# Minduino_A.net
KiCad netlist of a schematic drawn in EAGLE
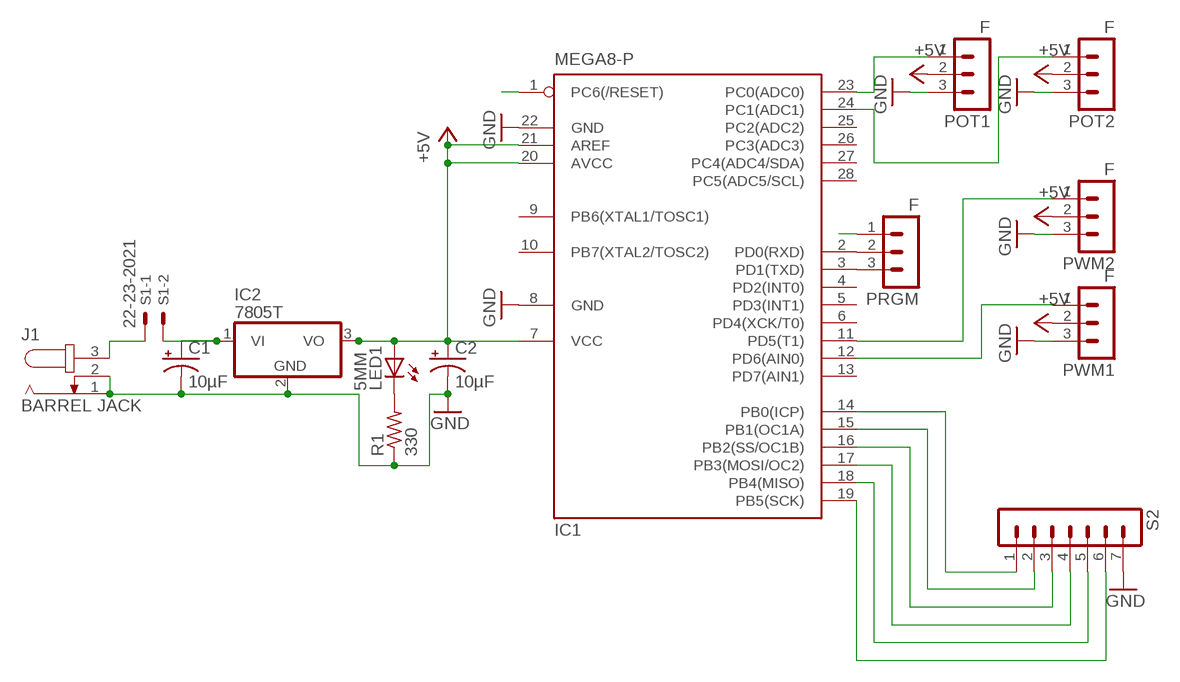
[diagram p0: schematic, sheet 1]

(export (version "E")
  (design (tool "Eeschema 10.0.6"))
  (components
    (comp (ref "C1")
      (value "10µF")
      (footprint "eagle-import:E2,5-5")
      (libsource (lib "eagle-import") (part "CPOL-USE2.5-5"))
    )
    (comp (ref "C2")
      (value "10µF")
      (footprint "eagle-import:E2,5-5")
      (libsource (lib "eagle-import") (part "CPOL-USE2.5-5"))
    )
    (comp (ref "IC1")
      (value "MEGA8-P")
      (footprint "eagle-import:DIL28-3")
      (libsource (lib "eagle-import") (part "MEGA8-P"))
    )
    (comp (ref "IC2")
      (value "7805T")
      (footprint "eagle-import:TO220H")
      (libsource (lib "eagle-import") (part "78T05"))
    )
    (comp (ref "J1")
      (value "BARREL JACK")
      (footprint "eagle-import:SPC4078")
      (libsource (lib "eagle-import") (part "JACK-PLUG1"))
    )
    (comp (ref "LED1")
      (value "5MM")
      (footprint "eagle-import:LED5MM")
      (libsource (lib "eagle-import") (part "LED5MM"))
    )
    (comp (ref "POT1")
      (value "F")
      (footprint "eagle-import:MA03-1")
      (libsource (lib "eagle-import") (part "MA03-1"))
    )
    (comp (ref "POT2")
      (value "F")
      (footprint "eagle-import:MA03-1")
      (libsource (lib "eagle-import") (part "MA03-1"))
    )
    (comp (ref "PRGM")
      (value "F")
      (footprint "eagle-import:MA03-1")
      (fields (field (name "OC_FARNELL") "unknown") (field (name "OC_NEWARK") "unknown"))
      (libsource (lib "eagle-import") (part "MA03-1"))
    )
    (comp (ref "PWM1")
      (value "F")
      (footprint "eagle-import:MA03-1")
      (libsource (lib "eagle-import") (part "MA03-1"))
    )
    (comp (ref "PWM2")
      (value "F")
      (footprint "eagle-import:MA03-1")
      (libsource (lib "eagle-import") (part "MA03-1"))
    )
    (comp (ref "R1")
      (value "330")
      (footprint "eagle-import:0204_5")
      (libsource (lib "eagle-import") (part "R-US_0204/5"))
    )
    (comp (ref "S1")
      (value "22-23-2021")
      (footprint "eagle-import:22-23-2021")
      (fields (field (name "MF") "MOLEX"))
      (libsource (lib "eagle-import") (part "22-23-2021"))
    )
    (comp (ref "S2")
      (value "MA07-1")
      (footprint "eagle-import:MA07-1")
      (libsource (lib "eagle-import") (part "MA07-1"))
    )
  )
  (nets
    (net (code "1") (name "+5V") (class "Default")
      (node (ref "C2") (pin "+") (pinfunction "+_+") (pintype "passive"))
      (node (ref "IC1") (pin "20") (pinfunction "AVCC_20") (pintype "power_in"))
      (node (ref "IC1") (pin "21") (pinfunction "AREF_21") (pintype "passive"))
      (node (ref "IC1") (pin "7") (pinfunction "VCC_7") (pintype "power_in"))
      (node (ref "IC2") (pin "3") (pinfunction "VO_3") (pintype "passive"))
      (node (ref "LED1") (pin "A") (pinfunction "A_A") (pintype "passive"))
      (node (ref "POT1") (pin "2") (pinfunction "2_2") (pintype "passive"))
      (node (ref "POT2") (pin "2") (pinfunction "2_2") (pintype "passive"))
      (node (ref "PWM1") (pin "2") (pinfunction "2_2") (pintype "passive"))
      (node (ref "PWM2") (pin "2") (pinfunction "2_2") (pintype "passive"))
    )
    (net (code "2") (name "/RST") (class "Default")
      (node (ref "IC1") (pin "1") (pinfunction "PC6(/RESET)_1") (pintype "bidirectional"))
      (node (ref "PRGM") (pin "1") (pinfunction "1_1") (pintype "passive"))
    )
    (net (code "3") (name "GND") (class "Default")
      (node (ref "C1") (pin "-") (pinfunction "-_-") (pintype "passive"))
      (node (ref "C2") (pin "-") (pinfunction "-_-") (pintype "passive"))
      (node (ref "IC1") (pin "22") (pinfunction "GND_22") (pintype "power_in"))
      (node (ref "IC1") (pin "8") (pinfunction "GND_8") (pintype "power_in"))
      (node (ref "IC2") (pin "2") (pinfunction "GND_2") (pintype "passive"))
      (node (ref "J1") (pin "1") (pinfunction "1_1") (pintype "passive"))
      (node (ref "J1") (pin "2") (pinfunction "2_2") (pintype "passive"))
      (node (ref "POT1") (pin "3") (pinfunction "3_3") (pintype "passive"))
      (node (ref "POT2") (pin "3") (pinfunction "3_3") (pintype "passive"))
      (node (ref "PWM1") (pin "3") (pinfunction "3_3") (pintype "passive"))
      (node (ref "PWM2") (pin "3") (pinfunction "3_3") (pintype "passive"))
      (node (ref "R1") (pin "1") (pinfunction "1_1") (pintype "passive"))
      (node (ref "S2") (pin "7") (pinfunction "7_7") (pintype "passive"))
    )
    (net (code "4") (name "Net-(IC1-PB0(ICP))") (class "Default")
      (node (ref "IC1") (pin "14") (pinfunction "PB0(ICP)_14") (pintype "bidirectional"))
      (node (ref "S2") (pin "1") (pinfunction "1_1") (pintype "passive"))
    )
    (net (code "5") (name "Net-(IC1-PB1(OC1A))") (class "Default")
      (node (ref "IC1") (pin "15") (pinfunction "PB1(OC1A)_15") (pintype "bidirectional"))
      (node (ref "S2") (pin "2") (pinfunction "2_2") (pintype "passive"))
    )
    (net (code "6") (name "Net-(IC1-PB2(SS{slash}OC1B))") (class "Default")
      (node (ref "IC1") (pin "16") (pinfunction "PB2(SS/OC1B)_16") (pintype "bidirectional"))
      (node (ref "S2") (pin "3") (pinfunction "3_3") (pintype "passive"))
    )
    (net (code "7") (name "Net-(IC1-PB3(MOSI{slash}OC2))") (class "Default")
      (node (ref "IC1") (pin "17") (pinfunction "PB3(MOSI/OC2)_17") (pintype "bidirectional"))
      (node (ref "S2") (pin "4") (pinfunction "4_4") (pintype "passive"))
    )
    (net (code "8") (name "Net-(IC1-PB4(MISO))") (class "Default")
      (node (ref "IC1") (pin "18") (pinfunction "PB4(MISO)_18") (pintype "bidirectional"))
      (node (ref "S2") (pin "5") (pinfunction "5_5") (pintype "passive"))
    )
    (net (code "9") (name "Net-(IC1-PB5(SCK))") (class "Default")
      (node (ref "IC1") (pin "19") (pinfunction "PB5(SCK)_19") (pintype "bidirectional"))
      (node (ref "S2") (pin "6") (pinfunction "6_6") (pintype "passive"))
    )
    (net (code "10") (name "Net-(IC1-PC0(ADC0))") (class "Default")
      (node (ref "IC1") (pin "23") (pinfunction "PC0(ADC0)_23") (pintype "bidirectional"))
      (node (ref "POT1") (pin "1") (pinfunction "1_1") (pintype "passive"))
    )
    (net (code "11") (name "Net-(IC1-PC1(ADC1))") (class "Default")
      (node (ref "IC1") (pin "24") (pinfunction "PC1(ADC1)_24") (pintype "bidirectional"))
      (node (ref "POT2") (pin "1") (pinfunction "1_1") (pintype "passive"))
    )
    (net (code "12") (name "Net-(IC1-PD0(RXD))") (class "Default")
      (node (ref "IC1") (pin "2") (pinfunction "PD0(RXD)_2") (pintype "bidirectional"))
      (node (ref "PRGM") (pin "2") (pinfunction "2_2") (pintype "passive"))
    )
    (net (code "13") (name "Net-(IC1-PD1(TXD))") (class "Default")
      (node (ref "IC1") (pin "3") (pinfunction "PD1(TXD)_3") (pintype "bidirectional"))
      (node (ref "PRGM") (pin "3") (pinfunction "3_3") (pintype "passive"))
    )
    (net (code "14") (name "Net-(IC1-PD5(T1))") (class "Default")
      (node (ref "IC1") (pin "11") (pinfunction "PD5(T1)_11") (pintype "bidirectional"))
      (node (ref "PWM2") (pin "1") (pinfunction "1_1") (pintype "passive"))
    )
    (net (code "15") (name "Net-(IC1-PD6(AIN0))") (class "Default")
      (node (ref "IC1") (pin "12") (pinfunction "PD6(AIN0)_12") (pintype "bidirectional"))
      (node (ref "PWM1") (pin "1") (pinfunction "1_1") (pintype "passive"))
    )
    (net (code "16") (name "Net-(IC2-VI)") (class "Default")
      (node (ref "C1") (pin "+") (pinfunction "+_+") (pintype "passive"))
      (node (ref "IC2") (pin "1") (pinfunction "VI_1") (pintype "input"))
      (node (ref "S1") (pin "2") (pinfunction "S_2") (pintype "passive"))
    )
    (net (code "17") (name "Net-(LED1-C)") (class "Default")
      (node (ref "LED1") (pin "K") (pinfunction "C_K") (pintype "passive"))
      (node (ref "R1") (pin "2") (pinfunction "2_2") (pintype "passive"))
    )
    (net (code "18") (name "Net-(S1A-S)") (class "Default")
      (node (ref "J1") (pin "3") (pinfunction "3_3") (pintype "passive"))
      (node (ref "S1") (pin "1") (pinfunction "S_1") (pintype "passive"))
    )
    (net (code "19") (name "unconnected-(IC1-PB6(XTAL1{slash}TOSC1)-Pad9)") (class "Default")
      (node (ref "IC1") (pin "9") (pinfunction "PB6(XTAL1/TOSC1)_9") (pintype "bidirectional"))
    )
    (net (code "20") (name "unconnected-(IC1-PB7(XTAL2{slash}TOSC2)-Pad10)") (class "Default")
      (node (ref "IC1") (pin "10") (pinfunction "PB7(XTAL2/TOSC2)_10") (pintype "bidirectional"))
    )
    (net (code "21") (name "unconnected-(IC1-PC2(ADC2)-Pad25)") (class "Default")
      (node (ref "IC1") (pin "25") (pinfunction "PC2(ADC2)_25") (pintype "bidirectional"))
    )
    (net (code "22") (name "unconnected-(IC1-PC3(ADC3)-Pad26)") (class "Default")
      (node (ref "IC1") (pin "26") (pinfunction "PC3(ADC3)_26") (pintype "bidirectional"))
    )
    (net (code "23") (name "unconnected-(IC1-PC4(ADC4{slash}SDA)-Pad27)") (class "Default")
      (node (ref "IC1") (pin "27") (pinfunction "PC4(ADC4/SDA)_27") (pintype "bidirectional"))
    )
    (net (code "24") (name "unconnected-(IC1-PC5(ADC5{slash}SCL)-Pad28)") (class "Default")
      (node (ref "IC1") (pin "28") (pinfunction "PC5(ADC5/SCL)_28") (pintype "bidirectional"))
    )
    (net (code "25") (name "unconnected-(IC1-PD2(INT0)-Pad4)") (class "Default")
      (node (ref "IC1") (pin "4") (pinfunction "PD2(INT0)_4") (pintype "bidirectional"))
    )
    (net (code "26") (name "unconnected-(IC1-PD3(INT1)-Pad5)") (class "Default")
      (node (ref "IC1") (pin "5") (pinfunction "PD3(INT1)_5") (pintype "bidirectional"))
    )
    (net (code "27") (name "unconnected-(IC1-PD4(XCK{slash}T0)-Pad6)") (class "Default")
      (node (ref "IC1") (pin "6") (pinfunction "PD4(XCK/T0)_6") (pintype "bidirectional"))
    )
    (net (code "28") (name "unconnected-(IC1-PD7(AIN1)-Pad13)") (class "Default")
      (node (ref "IC1") (pin "13") (pinfunction "PD7(AIN1)_13") (pintype "bidirectional"))
    )
  )
)
